# opto-isolated_adapter.net
KiCad netlist of a schematic drawn in EAGLE
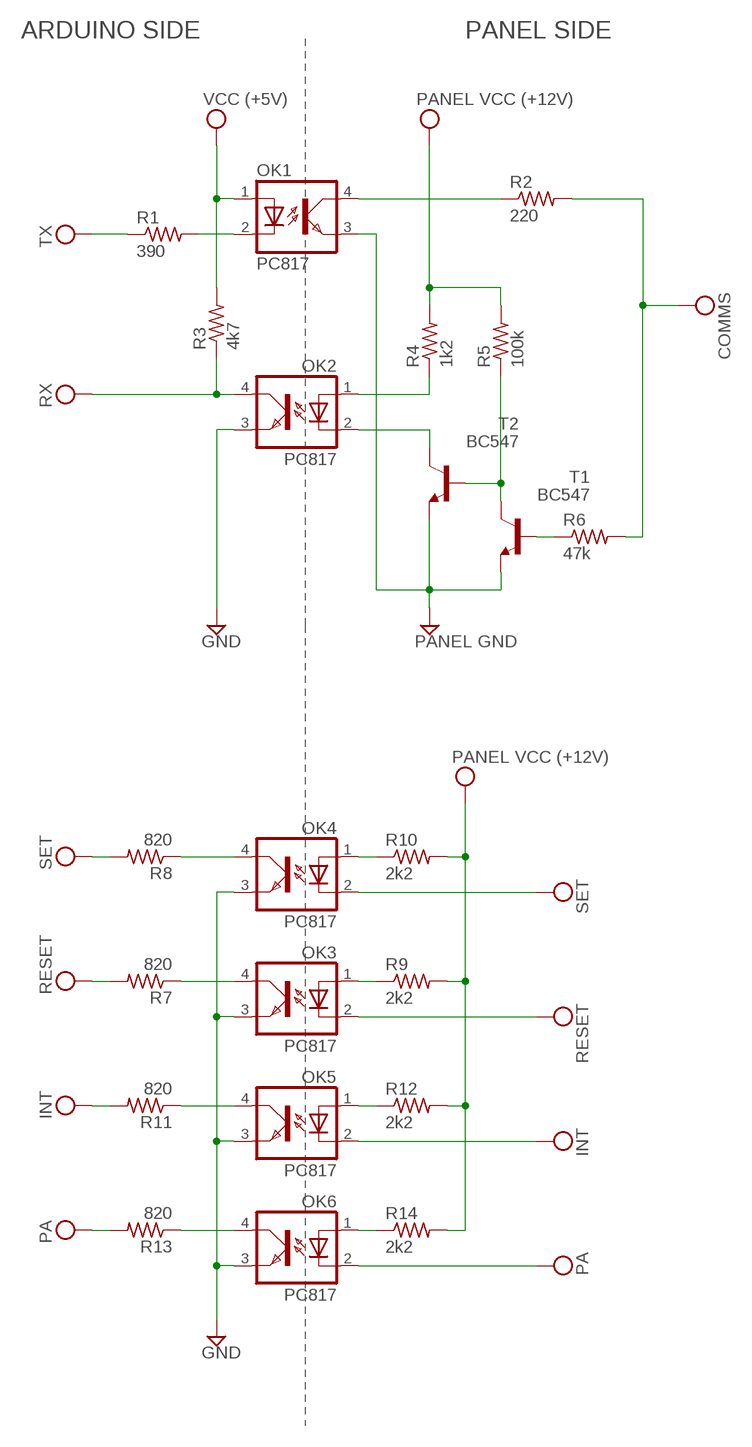
[diagram p0: schematic, sheet 1]

(export (version "E")
  (design (tool "Eeschema 10.0.6"))
  (components
    (comp (ref "OK1")
      (value "PC817")
      (footprint "eagle-import:DIL04")
      (fields (field (name "MPN") "PC817X4J000F"))
      (libsource (lib "eagle-import") (part "PC817"))
    )
    (comp (ref "OK2")
      (value "PC817")
      (footprint "eagle-import:DIL04")
      (fields (field (name "MPN") "PC817X4J000F"))
      (libsource (lib "eagle-import") (part "PC817"))
    )
    (comp (ref "OK3")
      (value "PC817")
      (footprint "eagle-import:DIL04")
      (fields (field (name "MPN") "PC817X4J000F"))
      (libsource (lib "eagle-import") (part "PC817"))
    )
    (comp (ref "OK4")
      (value "PC817")
      (footprint "eagle-import:DIL04")
      (fields (field (name "MPN") "PC817X4J000F"))
      (libsource (lib "eagle-import") (part "PC817"))
    )
    (comp (ref "OK5")
      (value "PC817")
      (footprint "eagle-import:DIL04")
      (fields (field (name "MPN") "PC817X4J000F"))
      (libsource (lib "eagle-import") (part "PC817"))
    )
    (comp (ref "OK6")
      (value "PC817")
      (footprint "eagle-import:DIL04")
      (fields (field (name "MPN") "PC817X4J000F"))
      (libsource (lib "eagle-import") (part "PC817"))
    )
    (comp (ref "R1")
      (value "390")
      (footprint "eagle-import:0207_12")
      (libsource (lib "eagle-import") (part "R-US_0207/12"))
    )
    (comp (ref "R2")
      (value "220")
      (footprint "eagle-import:0207_12")
      (libsource (lib "eagle-import") (part "R-US_0207/12"))
    )
    (comp (ref "R3")
      (value "4k7")
      (footprint "eagle-import:0207_12")
      (libsource (lib "eagle-import") (part "R-US_0207/12"))
    )
    (comp (ref "R4")
      (value "1k2")
      (footprint "eagle-import:0207_12")
      (libsource (lib "eagle-import") (part "R-US_0207/12"))
    )
    (comp (ref "R5")
      (value "100k")
      (footprint "eagle-import:0207_12")
      (libsource (lib "eagle-import") (part "R-US_0207/12"))
    )
    (comp (ref "R6")
      (value "47k")
      (footprint "eagle-import:0207_12")
      (libsource (lib "eagle-import") (part "R-US_0207/12"))
    )
    (comp (ref "R7")
      (value "820")
      (footprint "eagle-import:0207_12")
      (libsource (lib "eagle-import") (part "R-US_0207/12"))
    )
    (comp (ref "R8")
      (value "820")
      (footprint "eagle-import:0207_12")
      (libsource (lib "eagle-import") (part "R-US_0207/12"))
    )
    (comp (ref "R9")
      (value "2k2")
      (footprint "eagle-import:0207_12")
      (libsource (lib "eagle-import") (part "R-US_0207/12"))
    )
    (comp (ref "R10")
      (value "2k2")
      (footprint "eagle-import:0207_12")
      (libsource (lib "eagle-import") (part "R-US_0207/12"))
    )
    (comp (ref "R11")
      (value "820")
      (footprint "eagle-import:0207_12")
      (libsource (lib "eagle-import") (part "R-US_0207/12"))
    )
    (comp (ref "R12")
      (value "2k2")
      (footprint "eagle-import:0207_12")
      (libsource (lib "eagle-import") (part "R-US_0207/12"))
    )
    (comp (ref "R13")
      (value "820")
      (footprint "eagle-import:0207_12")
      (libsource (lib "eagle-import") (part "R-US_0207/12"))
    )
    (comp (ref "R14")
      (value "2k2")
      (footprint "eagle-import:0207_12")
      (libsource (lib "eagle-import") (part "R-US_0207/12"))
    )
    (comp (ref "T1")
      (value "BC547")
      (footprint "eagle-import:TO92")
      (libsource (lib "eagle-import") (part "BC547"))
    )
    (comp (ref "T2")
      (value "BC547")
      (footprint "eagle-import:TO92")
      (libsource (lib "eagle-import") (part "BC547"))
    )
  )
  (nets
    (net (code "1") (name "COMMS") (class "Default")
      (node (ref "OK1") (pin "1") (pinfunction "A_1") (pintype "passive"))
      (node (ref "OK2") (pin "4") (pinfunction "COL_4") (pintype "passive"))
      (node (ref "OK3") (pin "2") (pinfunction "C_2") (pintype "passive"))
      (node (ref "OK4") (pin "2") (pinfunction "C_2") (pintype "passive"))
      (node (ref "OK5") (pin "2") (pinfunction "C_2") (pintype "passive"))
      (node (ref "OK6") (pin "2") (pinfunction "C_2") (pintype "passive"))
      (node (ref "R1") (pin "1") (pinfunction "1_1") (pintype "passive"))
      (node (ref "R10") (pin "2") (pinfunction "2_2") (pintype "passive"))
      (node (ref "R11") (pin "2") (pinfunction "2_2") (pintype "passive"))
      (node (ref "R12") (pin "2") (pinfunction "2_2") (pintype "passive"))
      (node (ref "R13") (pin "2") (pinfunction "2_2") (pintype "passive"))
      (node (ref "R14") (pin "2") (pinfunction "2_2") (pintype "passive"))
      (node (ref "R2") (pin "2") (pinfunction "2_2") (pintype "passive"))
      (node (ref "R3") (pin "1") (pinfunction "1_1") (pintype "passive"))
      (node (ref "R3") (pin "2") (pinfunction "2_2") (pintype "passive"))
      (node (ref "R4") (pin "2") (pinfunction "2_2") (pintype "passive"))
      (node (ref "R5") (pin "2") (pinfunction "2_2") (pintype "passive"))
      (node (ref "R6") (pin "2") (pinfunction "2_2") (pintype "passive"))
      (node (ref "R7") (pin "2") (pinfunction "2_2") (pintype "passive"))
      (node (ref "R8") (pin "2") (pinfunction "2_2") (pintype "passive"))
      (node (ref "R9") (pin "2") (pinfunction "2_2") (pintype "passive"))
    )
    (net (code "2") (name "GND") (class "Default")
      (node (ref "OK1") (pin "3") (pinfunction "EMIT_3") (pintype "passive"))
      (node (ref "OK2") (pin "3") (pinfunction "EMIT_3") (pintype "passive"))
      (node (ref "OK3") (pin "3") (pinfunction "EMIT_3") (pintype "passive"))
      (node (ref "OK4") (pin "3") (pinfunction "EMIT_3") (pintype "passive"))
      (node (ref "OK5") (pin "3") (pinfunction "EMIT_3") (pintype "passive"))
      (node (ref "OK6") (pin "3") (pinfunction "EMIT_3") (pintype "passive"))
      (node (ref "T1") (pin "1") (pinfunction "E_1") (pintype "passive"))
      (node (ref "T2") (pin "1") (pinfunction "E_1") (pintype "passive"))
    )
    (net (code "3") (name "Net-(OK1-C)") (class "Default")
      (node (ref "OK1") (pin "2") (pinfunction "C_2") (pintype "passive"))
      (node (ref "R1") (pin "2") (pinfunction "2_2") (pintype "passive"))
    )
    (net (code "4") (name "Net-(OK1-COL)") (class "Default")
      (node (ref "OK1") (pin "4") (pinfunction "COL_4") (pintype "passive"))
      (node (ref "R2") (pin "1") (pinfunction "1_1") (pintype "passive"))
    )
    (net (code "5") (name "Net-(OK2-A)") (class "Default")
      (node (ref "OK2") (pin "1") (pinfunction "A_1") (pintype "passive"))
      (node (ref "R4") (pin "1") (pinfunction "1_1") (pintype "passive"))
    )
    (net (code "6") (name "Net-(OK2-C)") (class "Default")
      (node (ref "OK2") (pin "2") (pinfunction "C_2") (pintype "passive"))
      (node (ref "T2") (pin "3") (pinfunction "C_3") (pintype "passive"))
    )
    (net (code "7") (name "Net-(OK3-A)") (class "Default")
      (node (ref "OK3") (pin "1") (pinfunction "A_1") (pintype "passive"))
      (node (ref "R9") (pin "1") (pinfunction "1_1") (pintype "passive"))
    )
    (net (code "8") (name "Net-(OK3-COL)") (class "Default")
      (node (ref "OK3") (pin "4") (pinfunction "COL_4") (pintype "passive"))
      (node (ref "R7") (pin "1") (pinfunction "1_1") (pintype "passive"))
    )
    (net (code "9") (name "Net-(OK4-A)") (class "Default")
      (node (ref "OK4") (pin "1") (pinfunction "A_1") (pintype "passive"))
      (node (ref "R10") (pin "1") (pinfunction "1_1") (pintype "passive"))
    )
    (net (code "10") (name "Net-(OK4-COL)") (class "Default")
      (node (ref "OK4") (pin "4") (pinfunction "COL_4") (pintype "passive"))
      (node (ref "R8") (pin "1") (pinfunction "1_1") (pintype "passive"))
    )
    (net (code "11") (name "Net-(OK5-A)") (class "Default")
      (node (ref "OK5") (pin "1") (pinfunction "A_1") (pintype "passive"))
      (node (ref "R12") (pin "1") (pinfunction "1_1") (pintype "passive"))
    )
    (net (code "12") (name "Net-(OK5-COL)") (class "Default")
      (node (ref "OK5") (pin "4") (pinfunction "COL_4") (pintype "passive"))
      (node (ref "R11") (pin "1") (pinfunction "1_1") (pintype "passive"))
    )
    (net (code "13") (name "Net-(OK6-A)") (class "Default")
      (node (ref "OK6") (pin "1") (pinfunction "A_1") (pintype "passive"))
      (node (ref "R14") (pin "1") (pinfunction "1_1") (pintype "passive"))
    )
    (net (code "14") (name "Net-(OK6-COL)") (class "Default")
      (node (ref "OK6") (pin "4") (pinfunction "COL_4") (pintype "passive"))
      (node (ref "R13") (pin "1") (pinfunction "1_1") (pintype "passive"))
    )
    (net (code "15") (name "Net-(T1-B)") (class "Default")
      (node (ref "R6") (pin "1") (pinfunction "1_1") (pintype "passive"))
      (node (ref "T1") (pin "2") (pinfunction "B_2") (pintype "passive"))
    )
    (net (code "16") (name "Net-(T1-C)") (class "Default")
      (node (ref "R5") (pin "1") (pinfunction "1_1") (pintype "passive"))
      (node (ref "T1") (pin "3") (pinfunction "C_3") (pintype "passive"))
      (node (ref "T2") (pin "2") (pinfunction "B_2") (pintype "passive"))
    )
  )
)
